# micD21_v51a1.net
KiCad netlist of a schematic drawn in EAGLE
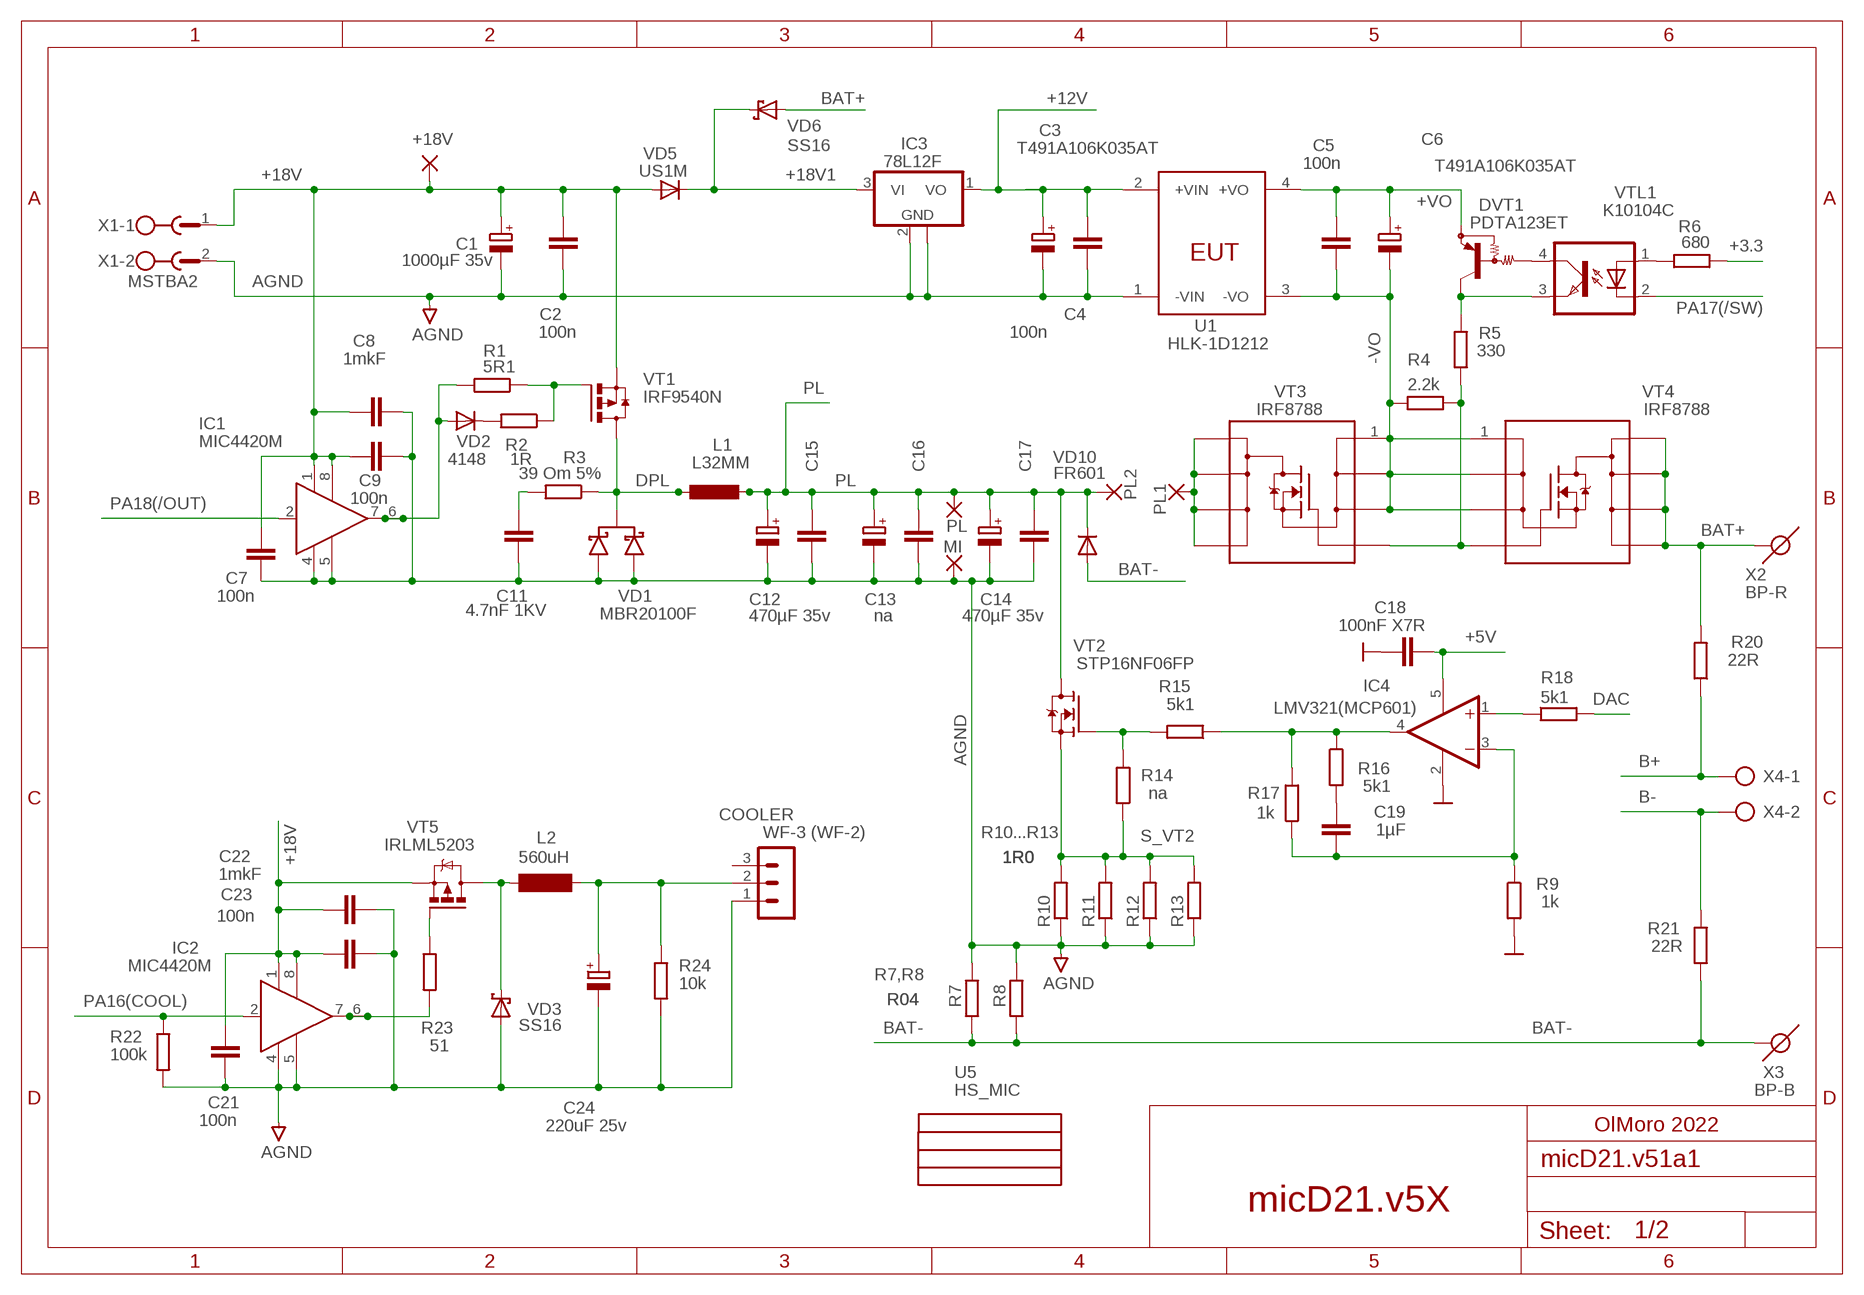
[diagram p0: schematic, sheet 1]
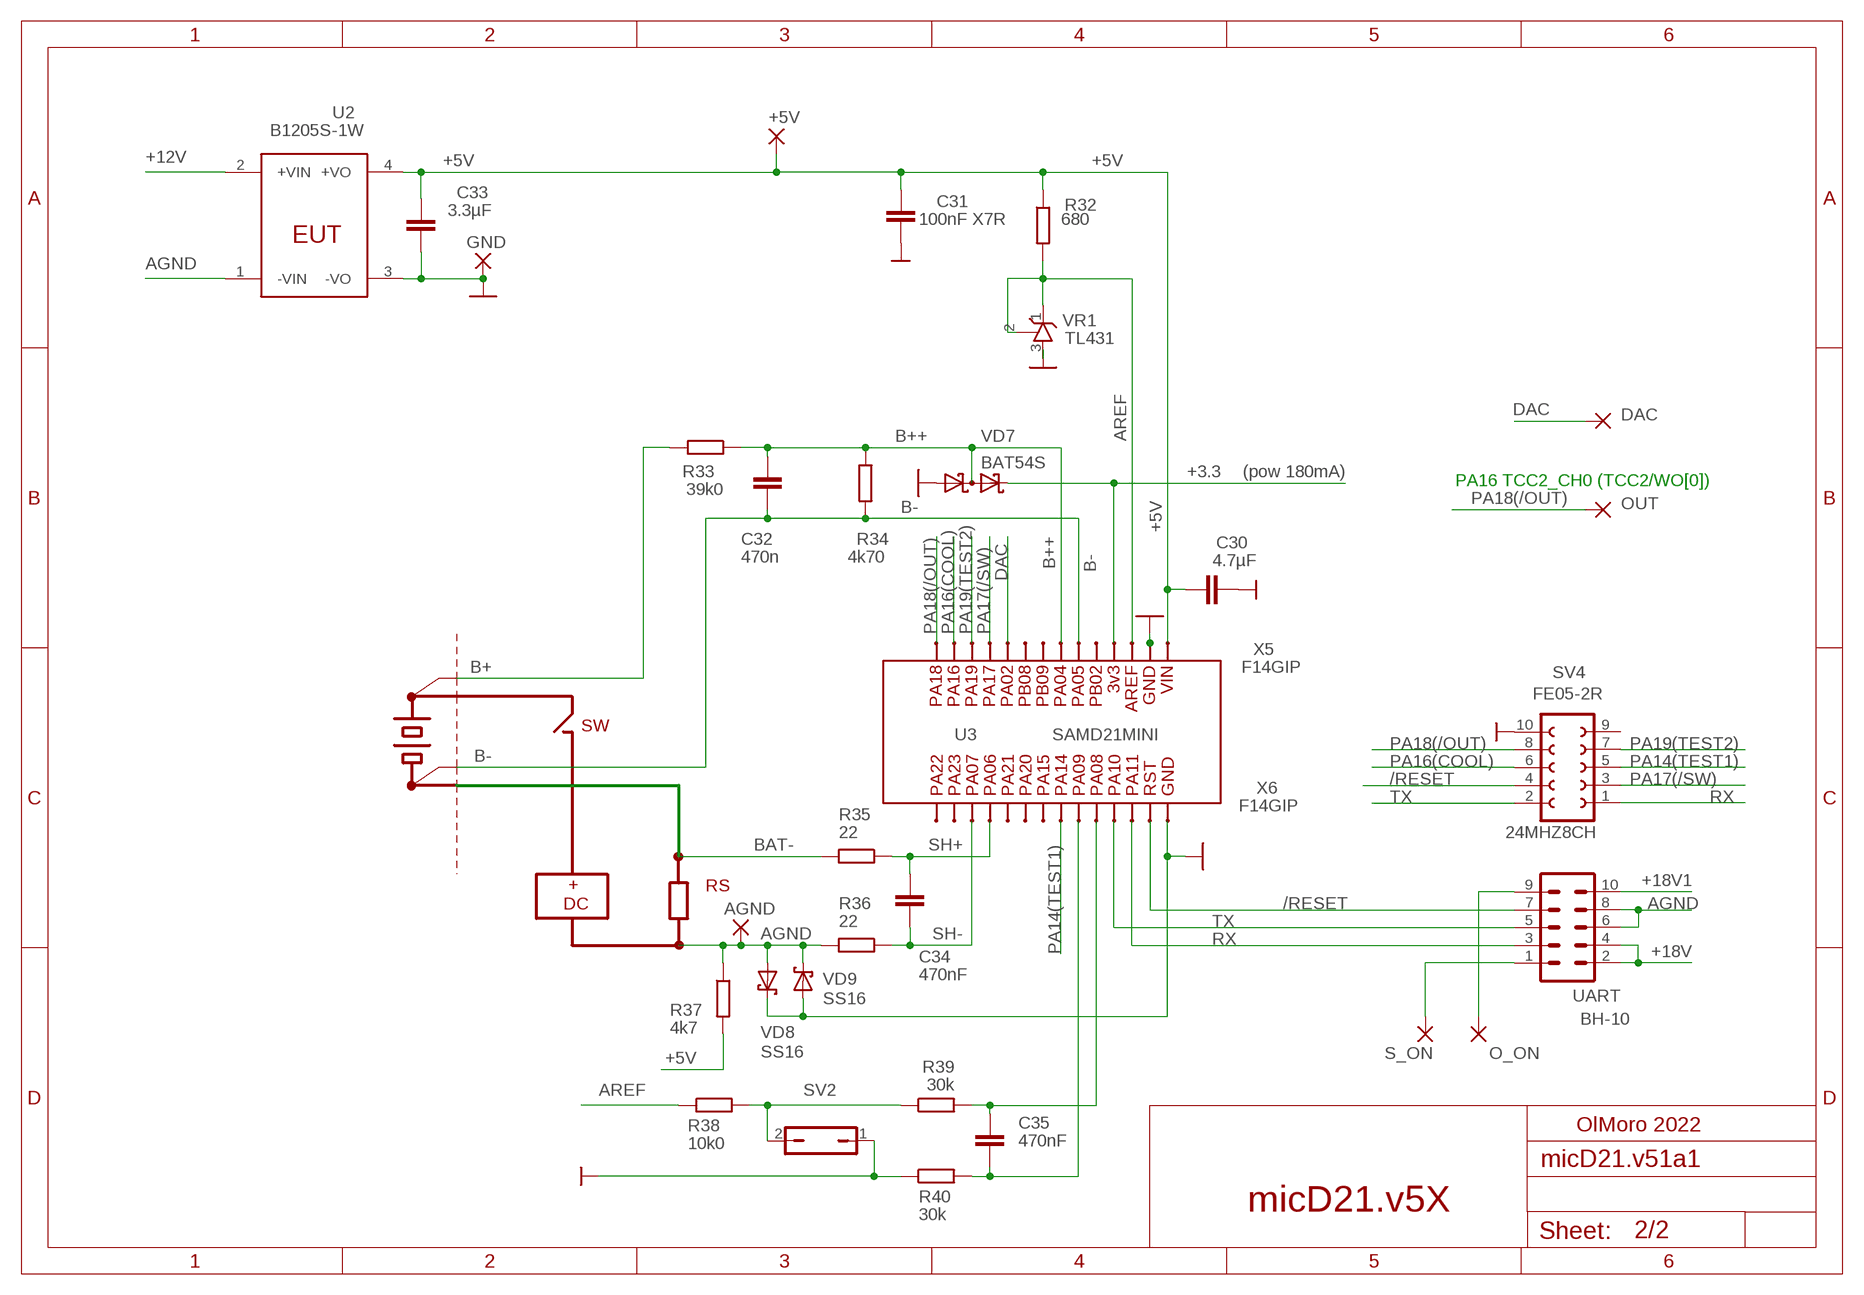
[diagram p1: schematic, sheet 2]

(export (version "E")
  (design (tool "Eeschema 10.0.6"))
  (components
    (comp (ref "+5V")
      (value "WIREPAD1,6/0,8")
      (footprint "eagle-import:1,6_0,8")
      (libsource (lib "eagle-import") (part "WIREPAD1,6/0,8"))
    )
    (comp (ref "24MHZ8CH")
      (value "DIAGNOSTICS")
      (footprint "eagle-import:DIAGNOSTICS")
      (libsource (lib "eagle-import") (part "DIAGNOSTICS"))
    )
    (comp (ref "AGND")
      (value "AGND")
      (footprint "eagle-import:4,16O1,6")
      (libsource (lib "eagle-import") (part "WIREPAD4,16O1,6"))
    )
    (comp (ref "C30")
      (value "4.7µF")
      (footprint "eagle-import:C0805")
      (libsource (lib "eagle-import") (part "C-EUC0805"))
    )
    (comp (ref "C31")
      (value "100nF X7R")
      (footprint "eagle-import:C0603")
      (libsource (lib "eagle-import") (part "C-EUC0603"))
    )
    (comp (ref "C32")
      (value "470n")
      (footprint "eagle-import:C0603")
      (libsource (lib "eagle-import") (part "C-EUC0603"))
    )
    (comp (ref "C33")
      (value "3.3µF")
      (footprint "eagle-import:C0805")
      (libsource (lib "eagle-import") (part "C-EUC0805"))
    )
    (comp (ref "C34")
      (value "470nF")
      (footprint "eagle-import:C0603")
      (libsource (lib "eagle-import") (part "C-EUC0603"))
    )
    (comp (ref "C35")
      (value "470nF")
      (footprint "eagle-import:C0805")
      (libsource (lib "eagle-import") (part "C-EUC0805"))
    )
    (comp (ref "DAC")
      (value "WIREPAD1,6/0,8")
      (footprint "eagle-import:1,6_0,8")
      (libsource (lib "eagle-import") (part "WIREPAD1,6/0,8"))
    )
    (comp (ref "GND")
      (value "GND")
      (footprint "eagle-import:4,16O1,6")
      (libsource (lib "eagle-import") (part "WIREPAD4,16O1,6"))
    )
    (comp (ref "OUT")
      (value "WIREPAD1,6/0,8")
      (footprint "eagle-import:1,6_0,8")
      (libsource (lib "eagle-import") (part "WIREPAD1,6/0,8"))
    )
    (comp (ref "O_ON")
      (value "WIREPAD1,6/0,8")
      (footprint "eagle-import:1,6_0,8")
      (libsource (lib "eagle-import") (part "WIREPAD1,6/0,8"))
    )
    (comp (ref "R32")
      (value "680")
      (footprint "eagle-import:R0603")
      (libsource (lib "eagle-import") (part "R-EU_R0603"))
    )
    (comp (ref "R33")
      (value "39k0")
      (footprint "eagle-import:R0603")
      (libsource (lib "eagle-import") (part "R-EU_R0603"))
    )
    (comp (ref "R34")
      (value "4k70")
      (footprint "eagle-import:R0603")
      (libsource (lib "eagle-import") (part "R-EU_R0603"))
    )
    (comp (ref "R35")
      (value "22")
      (footprint "eagle-import:R0603")
      (libsource (lib "eagle-import") (part "R-EU_R0603"))
    )
    (comp (ref "R36")
      (value "22")
      (footprint "eagle-import:R0603")
      (libsource (lib "eagle-import") (part "R-EU_R0603"))
    )
    (comp (ref "R37")
      (value "4k7")
      (footprint "eagle-import:R0603")
      (libsource (lib "eagle-import") (part "R-EU_R0603"))
    )
    (comp (ref "R38")
      (value "10k0")
      (footprint "eagle-import:R0603")
      (libsource (lib "eagle-import") (part "R-EU_R0603"))
    )
    (comp (ref "R39")
      (value "30k")
      (footprint "eagle-import:R0603")
      (libsource (lib "eagle-import") (part "R-EU_R0603"))
    )
    (comp (ref "R40")
      (value "30k")
      (footprint "eagle-import:R0603")
      (libsource (lib "eagle-import") (part "R-EU_R0603"))
    )
    (comp (ref "SV2")
      (value "JP1Q")
      (footprint "eagle-import:JP1")
      (libsource (lib "eagle-import") (part "JP1Q"))
    )
    (comp (ref "SV4")
      (value "FE05-2R")
      (footprint "eagle-import:FE05-2R")
      (libsource (lib "eagle-import") (part "FE05-2R"))
    )
    (comp (ref "S_ON")
      (value "WIREPAD1,6/0,8")
      (footprint "eagle-import:1,6_0,8")
      (libsource (lib "eagle-import") (part "WIREPAD1,6/0,8"))
    )
    (comp (ref "U2")
      (value "B1205S-1W")
      (footprint "eagle-import:HLK-1D1212")
      (libsource (lib "eagle-import") (part "HLK-1D1212"))
    )
    (comp (ref "U3")
      (value "SAMD21MINI")
      (footprint "eagle-import:SAMD21MINI")
      (libsource (lib "eagle-import") (part "SAMD21MINI"))
    )
    (comp (ref "UART")
      (value "BH-10")
      (footprint "eagle-import:ML10")
      (libsource (lib "eagle-import") (part "ML10"))
    )
    (comp (ref "VD7")
      (value "BAT54S")
      (footprint "eagle-import:SOT23")
      (libsource (lib "eagle-import") (part "BAT54S"))
    )
    (comp (ref "VD8")
      (value "SS16")
      (footprint "eagle-import:DO214AC")
      (libsource (lib "eagle-import") (part "SS16"))
    )
    (comp (ref "VD9")
      (value "SS16")
      (footprint "eagle-import:DO214AC")
      (libsource (lib "eagle-import") (part "SS16"))
    )
    (comp (ref "VR1")
      (value "TL431")
      (footprint "eagle-import:SOT23")
      (libsource (lib "eagle-import") (part "TL431-SOT23-3"))
    )
    (comp (ref "X5")
      (value "F14GIP")
      (footprint "eagle-import:F14GIP")
      (libsource (lib "eagle-import") (part "F14GIP"))
    )
    (comp (ref "X6")
      (value "F14GIP")
      (footprint "eagle-import:F14GIP")
      (libsource (lib "eagle-import") (part "F14GIP"))
    )
    (comp (ref "+18V")
      (value "WIREPAD1,6/0,8")
      (footprint "eagle-import:1,6_0,8")
      (libsource (lib "eagle-import") (part "WIREPAD1,6/0,8"))
    )
    (comp (ref "C1")
      (value "1000µF 35v")
      (footprint "eagle-import:E5-10,5")
      (libsource (lib "eagle-import") (part "CPOL-EUE5-10.5"))
    )
    (comp (ref "C2")
      (value "100n")
      (footprint "eagle-import:C0805")
      (libsource (lib "eagle-import") (part "C-EUC0805"))
    )
    (comp (ref "C3")
      (value "T491A106K035AT")
      (footprint "eagle-import:CT3528")
      (libsource (lib "eagle-import") (part "CPOL-EUCT3528"))
    )
    (comp (ref "C4")
      (value "100n")
      (footprint "eagle-import:C0603")
      (libsource (lib "eagle-import") (part "C-EUC0603"))
    )
    (comp (ref "C5")
      (value "100n")
      (footprint "eagle-import:C0603")
      (libsource (lib "eagle-import") (part "C-EUC0603"))
    )
    (comp (ref "C6")
      (value "T491A106K035AT")
      (footprint "eagle-import:CT3528")
      (libsource (lib "eagle-import") (part "CPOL-EUCT3528"))
    )
    (comp (ref "C7")
      (value "100n")
      (footprint "eagle-import:C0603")
      (libsource (lib "eagle-import") (part "C-EUC0603"))
    )
    (comp (ref "C8")
      (value "1mkF")
      (footprint "eagle-import:C0603")
      (libsource (lib "eagle-import") (part "C-EUC0603"))
    )
    (comp (ref "C9")
      (value "100n")
      (footprint "eagle-import:C0603")
      (libsource (lib "eagle-import") (part "C-EUC0603"))
    )
    (comp (ref "C11")
      (value "4.7nF 1KV")
      (footprint "eagle-import:C102-064X133")
      (libsource (lib "eagle-import") (part "C-EU102-064X133"))
    )
    (comp (ref "C12")
      (value "470µF 35v")
      (footprint "eagle-import:E5-10,5")
      (libsource (lib "eagle-import") (part "CPOL-EUE5-10.5"))
    )
    (comp (ref "C13")
      (value "na")
      (footprint "eagle-import:E5-13")
      (libsource (lib "eagle-import") (part "CPOL-EUE5-13"))
    )
    (comp (ref "C14")
      (value "470µF 35v")
      (footprint "eagle-import:E5-10,5")
      (libsource (lib "eagle-import") (part "CPOL-EUE5-10.5"))
    )
    (comp (ref "C15")
      (value "1mkF")
      (footprint "eagle-import:C0805")
      (libsource (lib "eagle-import") (part "C-EUC0805"))
    )
    (comp (ref "C16")
      (value "1mkF")
      (footprint "eagle-import:C0805")
      (libsource (lib "eagle-import") (part "C-EUC0805"))
    )
    (comp (ref "C17")
      (value "1mkF")
      (footprint "eagle-import:C0805")
      (libsource (lib "eagle-import") (part "C-EUC0805"))
    )
    (comp (ref "C18")
      (value "100nF X7R")
      (footprint "eagle-import:C0603")
      (libsource (lib "eagle-import") (part "C-EUC0603"))
    )
    (comp (ref "C19")
      (value "1µF")
      (footprint "eagle-import:C0603")
      (libsource (lib "eagle-import") (part "C-EUC0603"))
    )
    (comp (ref "C21")
      (value "100n")
      (footprint "eagle-import:C0603")
      (libsource (lib "eagle-import") (part "C-EUC0603"))
    )
    (comp (ref "C22")
      (value "1mkF")
      (footprint "eagle-import:C0603")
      (libsource (lib "eagle-import") (part "C-EUC0603"))
    )
    (comp (ref "C23")
      (value "100n")
      (footprint "eagle-import:C0603")
      (libsource (lib "eagle-import") (part "C-EUC0603"))
    )
    (comp (ref "C24")
      (value "220uF 25v")
      (footprint "eagle-import:E5-8,5")
      (libsource (lib "eagle-import") (part "CPOL-EUE5-8.5"))
    )
    (comp (ref "COOLER")
      (value "WF-3 (WF-2)")
      (footprint "eagle-import:WF-3")
      (libsource (lib "eagle-import") (part "WF-3"))
    )
    (comp (ref "DVT1")
      (value "PDTA123ET")
      (footprint "eagle-import:SC59-BEC")
      (libsource (lib "eagle-import") (part "MUN2113T1"))
    )
    (comp (ref "IC1")
      (value "MIC4420M")
      (footprint "eagle-import:SO-08")
      (libsource (lib "eagle-import") (part "MIC4420M"))
    )
    (comp (ref "IC2")
      (value "MIC4420M")
      (footprint "eagle-import:SO-08")
      (libsource (lib "eagle-import") (part "MIC4420M"))
    )
    (comp (ref "IC3")
      (value "78L12F")
      (footprint "eagle-import:SOT89")
      (libsource (lib "eagle-import") (part "78LF12"))
    )
    (comp (ref "IC4")
      (value "LMV321(MCP601)")
      (footprint "eagle-import:SOT23-5")
      (libsource (lib "eagle-import") (part "LM321?MF"))
    )
    (comp (ref "L1")
      (value "L32MM")
      (footprint "eagle-import:L22MM")
      (libsource (lib "eagle-import") (part "L32MM"))
    )
    (comp (ref "L2")
      (value "560uH")
      (footprint "eagle-import:BS11")
      (libsource (lib "eagle-import") (part "BS11"))
    )
    (comp (ref "MI")
      (value "WIREPAD4,16O1,6")
      (footprint "eagle-import:4,16O1,6")
      (libsource (lib "eagle-import") (part "WIREPAD4,16O1,6"))
    )
    (comp (ref "PL")
      (value "WIREPAD4,16O1,6")
      (footprint "eagle-import:4,16O1,6")
      (libsource (lib "eagle-import") (part "WIREPAD4,16O1,6"))
    )
    (comp (ref "PL1")
      (value "WIREPAD2,54/0,8")
      (footprint "eagle-import:2,54_0,8")
      (libsource (lib "eagle-import") (part "WIREPAD2,54/0,8"))
    )
    (comp (ref "PL2")
      (value "WIREPAD2,54/0,8")
      (footprint "eagle-import:2,54_0,8")
      (libsource (lib "eagle-import") (part "WIREPAD2,54/0,8"))
    )
    (comp (ref "R1")
      (value "5R1")
      (footprint "eagle-import:R0805")
      (libsource (lib "eagle-import") (part "R-EU_R0805"))
    )
    (comp (ref "R2")
      (value "1R")
      (footprint "eagle-import:R0805")
      (libsource (lib "eagle-import") (part "R-EU_R0805"))
    )
    (comp (ref "R3")
      (value "39 Om 5%")
      (footprint "eagle-import:0515_20")
      (libsource (lib "eagle-import") (part "R-0515/20"))
    )
    (comp (ref "R4")
      (value "2.2k")
      (footprint "eagle-import:R0603")
      (libsource (lib "eagle-import") (part "R-EU_R0603"))
    )
    (comp (ref "R5")
      (value "330")
      (footprint "eagle-import:R0603")
      (libsource (lib "eagle-import") (part "R-EU_R0603"))
    )
    (comp (ref "R6")
      (value "680")
      (footprint "eagle-import:R0603")
      (libsource (lib "eagle-import") (part "R-EU_R0603"))
    )
    (comp (ref "R7")
      (value "R04")
      (footprint "eagle-import:R2512")
      (libsource (lib "eagle-import") (part "R-EU_R2512"))
    )
    (comp (ref "R8")
      (value "R04")
      (footprint "eagle-import:R2512")
      (libsource (lib "eagle-import") (part "R-EU_R2512"))
    )
    (comp (ref "R9")
      (value "1k")
      (footprint "eagle-import:R0603")
      (libsource (lib "eagle-import") (part "R-EU_R0603"))
    )
    (comp (ref "R10")
      (value "1R0")
      (footprint "eagle-import:R2512")
      (libsource (lib "eagle-import") (part "R-EU_R2512"))
    )
    (comp (ref "R11")
      (value "1R0")
      (footprint "eagle-import:R2512")
      (libsource (lib "eagle-import") (part "R-EU_R2512"))
    )
    (comp (ref "R12")
      (value "1R0")
      (footprint "eagle-import:R2512")
      (libsource (lib "eagle-import") (part "R-EU_R2512"))
    )
    (comp (ref "R13")
      (value "1R0")
      (footprint "eagle-import:R2512")
      (libsource (lib "eagle-import") (part "R-EU_R2512"))
    )
    (comp (ref "R14")
      (value "na")
      (footprint "eagle-import:R0603")
      (libsource (lib "eagle-import") (part "R-EU_R0603"))
    )
    (comp (ref "R15")
      (value "5k1")
      (footprint "eagle-import:R0603")
      (libsource (lib "eagle-import") (part "R-EU_R0603"))
    )
    (comp (ref "R16")
      (value "5k1")
      (footprint "eagle-import:R0603")
      (libsource (lib "eagle-import") (part "R-EU_R0603"))
    )
    (comp (ref "R17")
      (value "1k")
      (footprint "eagle-import:R0603")
      (libsource (lib "eagle-import") (part "R-EU_R0603"))
    )
    (comp (ref "R18")
      (value "5k1")
      (footprint "eagle-import:R0603")
      (libsource (lib "eagle-import") (part "R-EU_R0603"))
    )
    (comp (ref "R20")
      (value "22R")
      (footprint "eagle-import:R0603")
      (libsource (lib "eagle-import") (part "R-EU_R0603"))
    )
    (comp (ref "R21")
      (value "22R")
      (footprint "eagle-import:R0603")
      (libsource (lib "eagle-import") (part "R-EU_R0603"))
    )
    (comp (ref "R22")
      (value "100k")
      (footprint "eagle-import:R0603")
      (libsource (lib "eagle-import") (part "R-EU_R0603"))
    )
    (comp (ref "R23")
      (value "51")
      (footprint "eagle-import:R0603")
      (libsource (lib "eagle-import") (part "R-EU_R0603"))
    )
    (comp (ref "R24")
      (value "10k")
      (footprint "eagle-import:R0603")
      (libsource (lib "eagle-import") (part "R-EU_R0603"))
    )
    (comp (ref "U1")
      (value "HLK-1D1212")
      (footprint "eagle-import:HLK-1D1212")
      (libsource (lib "eagle-import") (part "HLK-1D1212"))
    )
    (comp (ref "U5")
      (value "HS_MIC")
      (footprint "eagle-import:HS-MIC")
      (libsource (lib "eagle-import") (part "HS_MIC"))
    )
    (comp (ref "VD1")
      (value "MBR20100F")
      (footprint "eagle-import:ITO220J")
      (libsource (lib "eagle-import") (part "MBR20100F"))
    )
    (comp (ref "VD2")
      (value "4148")
      (footprint "eagle-import:SMADIODE")
      (libsource (lib "eagle-import") (part "DIODESMA"))
    )
    (comp (ref "VD3")
      (value "SS16")
      (footprint "eagle-import:DO214AC")
      (libsource (lib "eagle-import") (part "SS16"))
    )
    (comp (ref "VD5")
      (value "US1M")
      (footprint "eagle-import:DO214AC")
      (libsource (lib "eagle-import") (part "US1M"))
    )
    (comp (ref "VD6")
      (value "SS16")
      (footprint "eagle-import:DO214AC")
      (libsource (lib "eagle-import") (part "SS16"))
    )
    (comp (ref "VD10")
      (value "FR601")
      (footprint "eagle-import:DIODE-1_P6-15")
      (libsource (lib "eagle-import") (part "DIODE-1_DIODE-P6-15"))
    )
    (comp (ref "VT1")
      (value "IRF9540N")
      (footprint "eagle-import:TO-220FP")
      (libsource (lib "eagle-import") (part "IRF9540N"))
    )
    (comp (ref "VT2")
      (value "STP16NF06FP")
      (footprint "eagle-import:TO-220FP")
      (libsource (lib "eagle-import") (part "STP16NF06FP"))
    )
    (comp (ref "VT3")
      (value "IRF8788")
      (footprint "eagle-import:SO-8")
      (libsource (lib "eagle-import") (part "IRF8788"))
    )
    (comp (ref "VT4")
      (value "IRF8788")
      (footprint "eagle-import:SO-8")
      (libsource (lib "eagle-import") (part "IRF8788"))
    )
    (comp (ref "VT5")
      (value "IRLML5203")
      (footprint "eagle-import:MICRO3")
      (libsource (lib "eagle-import") (part "IRLML5203"))
    )
    (comp (ref "VTL1")
      (value "K10104C")
      (footprint "eagle-import:SMD4-7")
      (libsource (lib "eagle-import") (part "SFH618?A-3X007"))
    )
    (comp (ref "X1")
      (value "MSTBA2")
      (footprint "eagle-import:MSTBA2")
      (fields (field (name "MF") "FARNELL") (field (name "MPN") "1757242"))
      (libsource (lib "eagle-import") (part "MSTBA2"))
    )
    (comp (ref "X2")
      (value "BP-R")
      (footprint "eagle-import:BP-R")
      (libsource (lib "eagle-import") (part "BP-R"))
    )
    (comp (ref "X3")
      (value "BP-B")
      (footprint "eagle-import:BP-B")
      (libsource (lib "eagle-import") (part "BP-B"))
    )
    (comp (ref "X4")
      (value "AK500/2-H")
      (footprint "eagle-import:AK500_2-H")
      (libsource (lib "eagle-import") (part "AK500/2-H"))
    )
  )
  (nets
    (net (code "1") (name "+3.3") (class "Default")
      (node (ref "R6") (pin "1") (pinfunction "1_1") (pintype "passive"))
      (node (ref "VD7") (pin "2") (pinfunction "C2_2") (pintype "passive"))
      (node (ref "X5") (pin "4") (pinfunction "4_4") (pintype "passive"))
    )
    (net (code "2") (name "+5V") (class "Default")
      (node (ref "+5V") (pin "1") (pinfunction "P_1") (pintype "passive"))
      (node (ref "C18") (pin "2") (pinfunction "2_2") (pintype "passive"))
      (node (ref "C30") (pin "1") (pinfunction "1_1") (pintype "passive"))
      (node (ref "C31") (pin "1") (pinfunction "1_1") (pintype "passive"))
      (node (ref "C33") (pin "1") (pinfunction "1_1") (pintype "passive"))
      (node (ref "IC4") (pin "5") (pinfunction "V+_5") (pintype "power_in"))
      (node (ref "R32") (pin "1") (pinfunction "1_1") (pintype "passive"))
      (node (ref "R37") (pin "2") (pinfunction "2_2") (pintype "passive"))
      (node (ref "U2") (pin "4") (pinfunction "+VO_4") (pintype "power_in"))
      (node (ref "X5") (pin "1") (pinfunction "1_1") (pintype "passive"))
    )
    (net (code "3") (name "+12V") (class "Default")
      (node (ref "C3") (pin "+") (pinfunction "+_+") (pintype "passive"))
      (node (ref "C4") (pin "2") (pinfunction "2_2") (pintype "passive"))
      (node (ref "IC3") (pin "1") (pinfunction "VO_1") (pintype "passive"))
      (node (ref "U1") (pin "2") (pinfunction "+VIN_2") (pintype "power_in"))
      (node (ref "U2") (pin "2") (pinfunction "+VIN_2") (pintype "power_in"))
    )
    (net (code "4") (name "+18V") (class "Default")
      (node (ref "+18V") (pin "1") (pinfunction "P_1") (pintype "passive"))
      (node (ref "C1") (pin "+") (pinfunction "+_+") (pintype "passive"))
      (node (ref "C2") (pin "2") (pinfunction "2_2") (pintype "passive"))
      (node (ref "C21") (pin "2") (pinfunction "2_2") (pintype "passive"))
      (node (ref "C22") (pin "2") (pinfunction "2_2") (pintype "passive"))
      (node (ref "C23") (pin "2") (pinfunction "2_2") (pintype "passive"))
      (node (ref "C7") (pin "2") (pinfunction "2_2") (pintype "passive"))
      (node (ref "C8") (pin "2") (pinfunction "2_2") (pintype "passive"))
      (node (ref "C9") (pin "2") (pinfunction "2_2") (pintype "passive"))
      (node (ref "IC1") (pin "1") (pinfunction "VS_1") (pintype "power_in"))
      (node (ref "IC1") (pin "8") (pinfunction "VS1_8") (pintype "power_in"))
      (node (ref "IC2") (pin "1") (pinfunction "VS_1") (pintype "power_in"))
      (node (ref "IC2") (pin "8") (pinfunction "VS1_8") (pintype "power_in"))
      (node (ref "UART") (pin "2") (pinfunction "2_2") (pintype "passive"))
      (node (ref "UART") (pin "4") (pinfunction "4_4") (pintype "passive"))
      (node (ref "VD5") (pin "A") (pinfunction "A_A") (pintype "passive"))
      (node (ref "VT1") (pin "3") (pinfunction "S_3") (pintype "passive"))
      (node (ref "VT5") (pin "2") (pinfunction "S_2") (pintype "passive"))
      (node (ref "X1") (pin "1") (pinfunction "1_1") (pintype "passive"))
    )
    (net (code "5") (name "+18V1") (class "Default")
      (node (ref "IC3") (pin "3") (pinfunction "VI_3") (pintype "input"))
      (node (ref "UART") (pin "10") (pinfunction "10_10") (pintype "passive"))
      (node (ref "VD5") (pin "C") (pinfunction "C_C") (pintype "passive"))
      (node (ref "VD6") (pin "C") (pinfunction "C_C") (pintype "passive"))
    )
    (net (code "6") (name "+VO") (class "Default")
      (node (ref "C5") (pin "2") (pinfunction "2_2") (pintype "passive"))
      (node (ref "C6") (pin "+") (pinfunction "+_+") (pintype "passive"))
      (node (ref "DVT1") (pin "E") (pinfunction "E_E") (pintype "passive"))
      (node (ref "U1") (pin "4") (pinfunction "+VO_4") (pintype "power_in"))
    )
    (net (code "7") (name "-VO") (class "Default")
      (node (ref "C5") (pin "1") (pinfunction "1_1") (pintype "passive"))
      (node (ref "C6") (pin "-") (pinfunction "-_-") (pintype "passive"))
      (node (ref "R4") (pin "2") (pinfunction "2_2") (pintype "passive"))
      (node (ref "U1") (pin "3") (pinfunction "-VO_3") (pintype "power_in"))
      (node (ref "VT3") (pin "1") (pinfunction "S_1") (pintype "passive"))
      (node (ref "VT3") (pin "2") (pinfunction "S_2") (pintype "passive"))
      (node (ref "VT3") (pin "3") (pinfunction "S_3") (pintype "passive"))
      (node (ref "VT4") (pin "1") (pinfunction "S_1") (pintype "passive"))
      (node (ref "VT4") (pin "2") (pinfunction "S_2") (pintype "passive"))
      (node (ref "VT4") (pin "3") (pinfunction "S_3") (pintype "passive"))
    )
    (net (code "8") (name "AGND") (class "Default")
      (node (ref "AGND") (pin "1") (pinfunction "P_1") (pintype "passive"))
      (node (ref "C1") (pin "-") (pinfunction "-_-") (pintype "passive"))
      (node (ref "C11") (pin "2") (pinfunction "2_2") (pintype "passive"))
      (node (ref "C12") (pin "-") (pinfunction "-_-") (pintype "passive"))
      (node (ref "C13") (pin "-") (pinfunction "-_-") (pintype "passive"))
      (node (ref "C14") (pin "-") (pinfunction "-_-") (pintype "passive"))
      (node (ref "C15") (pin "2") (pinfunction "2_2") (pintype "passive"))
      (node (ref "C16") (pin "2") (pinfunction "2_2") (pintype "passive"))
      (node (ref "C17") (pin "2") (pinfunction "2_2") (pintype "passive"))
      (node (ref "C2") (pin "1") (pinfunction "1_1") (pintype "passive"))
      (node (ref "C21") (pin "1") (pinfunction "1_1") (pintype "passive"))
      (node (ref "C22") (pin "1") (pinfunction "1_1") (pintype "passive"))
      (node (ref "C23") (pin "1") (pinfunction "1_1") (pintype "passive"))
      (node (ref "C24") (pin "-") (pinfunction "-_-") (pintype "passive"))
      (node (ref "C3") (pin "-") (pinfunction "-_-") (pintype "passive"))
      (node (ref "C4") (pin "1") (pinfunction "1_1") (pintype "passive"))
      (node (ref "C7") (pin "1") (pinfunction "1_1") (pintype "passive"))
      (node (ref "C8") (pin "1") (pinfunction "1_1") (pintype "passive"))
      (node (ref "C9") (pin "1") (pinfunction "1_1") (pintype "passive"))
      (node (ref "COOLER") (pin "1") (pinfunction "1_1") (pintype "passive"))
      (node (ref "IC1") (pin "4") (pinfunction "GND_4") (pintype "power_in"))
      (node (ref "IC1") (pin "5") (pinfunction "GND1_5") (pintype "power_in"))
      (node (ref "IC2") (pin "4") (pinfunction "GND_4") (pintype "power_in"))
      (node (ref "IC2") (pin "5") (pinfunction "GND1_5") (pintype "power_in"))
      (node (ref "IC3") (pin "2") (pinfunction "GND_2") (pintype "passive"))
      (node (ref "IC3") (pin "2@1") (pinfunction "GND_2@1") (pintype "passive"))
      (node (ref "MI") (pin "1") (pinfunction "P_1") (pintype "passive"))
      (node (ref "R10") (pin "1") (pinfunction "1_1") (pintype "passive"))
      (node (ref "R11") (pin "1") (pinfunction "1_1") (pintype "passive"))
      (node (ref "R12") (pin "1") (pinfunction "1_1") (pintype "passive"))
      (node (ref "R13") (pin "1") (pinfunction "1_1") (pintype "passive"))
      (node (ref "R22") (pin "2") (pinfunction "2_2") (pintype "passive"))
      (node (ref "R24") (pin "2") (pinfunction "2_2") (pintype "passive"))
      (node (ref "R36") (pin "2") (pinfunction "2_2") (pintype "passive"))
      (node (ref "R37") (pin "1") (pinfunction "1_1") (pintype "passive"))
      (node (ref "R7") (pin "2") (pinfunction "2_2") (pintype "passive"))
      (node (ref "R8") (pin "2") (pinfunction "2_2") (pintype "passive"))
      (node (ref "U1") (pin "1") (pinfunction "-VIN_1") (pintype "power_in"))
      (node (ref "U2") (pin "1") (pinfunction "-VIN_1") (pintype "power_in"))
      (node (ref "UART") (pin "6") (pinfunction "6_6") (pintype "passive"))
      (node (ref "UART") (pin "8") (pinfunction "8_8") (pintype "passive"))
      (node (ref "VD1") (pin "1") (pinfunction "A1_1") (pintype "passive"))
      (node (ref "VD1") (pin "3") (pinfunction "A2_3") (pintype "passive"))
      (node (ref "VD3") (pin "A") (pinfunction "A_A") (pintype "passive"))
      (node (ref "VD8") (pin "A") (pinfunction "A_A") (pintype "passive"))
      (node (ref "VD9") (pin "C") (pinfunction "C_C") (pintype "passive"))
      (node (ref "X1") (pin "2") (pinfunction "1_2") (pintype "passive"))
    )
    (net (code "9") (name "AREF") (class "Default")
      (node (ref "R32") (pin "2") (pinfunction "2_2") (pintype "passive"))
      (node (ref "R38") (pin "1") (pinfunction "1_1") (pintype "passive"))
      (node (ref "VR1") (pin "1") (pinfunction "C_1") (pintype "passive"))
      (node (ref "VR1") (pin "2") (pinfunction "R_2") (pintype "passive"))
      (node (ref "X5") (pin "3") (pinfunction "3_3") (pintype "passive"))
    )
    (net (code "10") (name "B+") (class "Default")
      (node (ref "R20") (pin "1") (pinfunction "1_1") (pintype "passive"))
      (node (ref "R33") (pin "2") (pinfunction "2_2") (pintype "passive"))
      (node (ref "X4") (pin "1") (pinfunction "KL_1") (pintype "passive"))
    )
    (net (code "11") (name "B++") (class "Default")
      (node (ref "C32") (pin "1") (pinfunction "1_1") (pintype "passive"))
      (node (ref "R33") (pin "1") (pinfunction "1_1") (pintype "passive"))
      (node (ref "R34") (pin "1") (pinfunction "1_1") (pintype "passive"))
      (node (ref "VD7") (pin "3") (pinfunction "C1A2_3") (pintype "passive"))
      (node (ref "X5") (pin "7") (pinfunction "7_7") (pintype "passive"))
    )
    (net (code "12") (name "B-") (class "Default")
      (node (ref "C32") (pin "2") (pinfunction "2_2") (pintype "passive"))
      (node (ref "R21") (pin "1") (pinfunction "1_1") (pintype "passive"))
      (node (ref "R34") (pin "2") (pinfunction "2_2") (pintype "passive"))
      (node (ref "X4") (pin "2") (pinfunction "KL_2") (pintype "passive"))
      (node (ref "X5") (pin "6") (pinfunction "6_6") (pintype "passive"))
    )
    (net (code "13") (name "BAT+") (class "Default")
      (node (ref "R20") (pin "2") (pinfunction "2_2") (pintype "passive"))
      (node (ref "VD6") (pin "A") (pinfunction "A_A") (pintype "passive"))
      (node (ref "VT4") (pin "5") (pinfunction "D_5") (pintype "passive"))
      (node (ref "VT4") (pin "6") (pinfunction "D_6") (pintype "passive"))
      (node (ref "VT4") (pin "7") (pinfunction "D_7") (pintype "passive"))
      (node (ref "VT4") (pin "8") (pinfunction "D_8") (pintype "passive"))
      (node (ref "X2") (pin "1") (pinfunction "P$1_1") (pintype "passive"))
    )
    (net (code "14") (name "BAT-") (class "Default")
      (node (ref "R21") (pin "2") (pinfunction "2_2") (pintype "passive"))
      (node (ref "R35") (pin "2") (pinfunction "2_2") (pintype "passive"))
      (node (ref "R7") (pin "1") (pinfunction "1_1") (pintype "passive"))
      (node (ref "R8") (pin "1") (pinfunction "1_1") (pintype "passive"))
      (node (ref "VD10") (pin "A") (pinfunction "A_A") (pintype "passive"))
      (node (ref "X3") (pin "1") (pinfunction "P$1_1") (pintype "passive"))
    )
    (net (code "15") (name "DAC") (class "Default")
      (node (ref "DAC") (pin "1") (pinfunction "P_1") (pintype "passive"))
      (node (ref "R18") (pin "2") (pinfunction "2_2") (pintype "passive"))
      (node (ref "X5") (pin "10") (pinfunction "10_10") (pintype "passive"))
    )
    (net (code "16") (name "DPL") (class "Default")
      (node (ref "L1") (pin "2@7") (pinfunction "2_2@7") (pintype "passive"))
      (node (ref "L1") (pin "2@8") (pinfunction "2_2@8") (pintype "passive"))
      (node (ref "R3") (pin "1") (pinfunction "1_1") (pintype "passive"))
      (node (ref "VD1") (pin "2") (pinfunction "C_2") (pintype "passive"))
      (node (ref "VT1") (pin "2") (pinfunction "D_2") (pintype "passive"))
    )
    (net (code "17") (name "GND") (class "Default")
      (node (ref "C18") (pin "1") (pinfunction "1_1") (pintype "passive"))
      (node (ref "C30") (pin "2") (pinfunction "2_2") (pintype "passive"))
      (node (ref "C31") (pin "2") (pinfunction "2_2") (pintype "passive"))
      (node (ref "C33") (pin "2") (pinfunction "2_2") (pintype "passive"))
      (node (ref "GND") (pin "1") (pinfunction "P_1") (pintype "passive"))
      (node (ref "IC4") (pin "2") (pinfunction "V-_2") (pintype "power_in"))
      (node (ref "R40") (pin "1") (pinfunction "1_1") (pintype "passive"))
      (node (ref "R9") (pin "2") (pinfunction "2_2") (pintype "passive"))
      (node (ref "SV2") (pin "1") (pinfunction "1_1") (pintype "passive"))
      (node (ref "SV4") (pin "10") (pinfunction "10_10") (pintype "passive"))
      (node (ref "U2") (pin "3") (pinfunction "-VO_3") (pintype "power_in"))
      (node (ref "VD7") (pin "1") (pinfunction "A1_1") (pintype "passive"))
      (node (ref "VD8") (pin "C") (pinfunction "C_C") (pintype "passive"))
      (node (ref "VD9") (pin "A") (pinfunction "A_A") (pintype "passive"))
      (node (ref "VR1") (pin "3") (pinfunction "A_3") (pintype "passive"))
      (node (ref "X5") (pin "2") (pinfunction "2_2") (pintype "passive"))
      (node (ref "X6") (pin "14") (pinfunction "14_14") (pintype "passive"))
    )
    (net (code "18") (name "Net-(C11-Pad1)") (class "Default")
      (node (ref "C11") (pin "1") (pinfunction "1_1") (pintype "passive"))
      (node (ref "R3") (pin "2") (pinfunction "2_2") (pintype "passive"))
    )
    (net (code "19") (name "Net-(C19-Pad1)") (class "Default")
      (node (ref "C19") (pin "1") (pinfunction "1_1") (pintype "passive"))
      (node (ref "R16") (pin "2") (pinfunction "2_2") (pintype "passive"))
    )
    (net (code "20") (name "Net-(C24-Pad+)") (class "Default")
      (node (ref "C24") (pin "+") (pinfunction "+_+") (pintype "passive"))
      (node (ref "COOLER") (pin "2") (pinfunction "2_2") (pintype "passive"))
      (node (ref "L2") (pin "2") (pinfunction "2_2") (pintype "passive"))
      (node (ref "R24") (pin "1") (pinfunction "1_1") (pintype "passive"))
    )
    (net (code "21") (name "Net-(C35-Pad1)") (class "Default")
      (node (ref "C35") (pin "1") (pinfunction "1_1") (pintype "passive"))
      (node (ref "R39") (pin "2") (pinfunction "2_2") (pintype "passive"))
      (node (ref "X6") (pin "10") (pinfunction "10_10") (pintype "passive"))
    )
    (net (code "22") (name "Net-(C35-Pad2)") (class "Default")
      (node (ref "C35") (pin "2") (pinfunction "2_2") (pintype "passive"))
      (node (ref "R40") (pin "2") (pinfunction "2_2") (pintype "passive"))
      (node (ref "X6") (pin "9") (pinfunction "9_9") (pintype "passive"))
    )
    (net (code "23") (name "Net-(IC1-OUT-Pad6)") (class "Default")
      (node (ref "IC1") (pin "6") (pinfunction "OUT_6") (pintype "passive"))
      (node (ref "IC1") (pin "7") (pinfunction "OUT_7") (pintype "passive"))
      (node (ref "R1") (pin "2") (pinfunction "2_2") (pintype "passive"))
      (node (ref "VD2") (pin "A") (pinfunction "A_A") (pintype "passive"))
    )
    (net (code "24") (name "Net-(IC2-OUT-Pad6)") (class "Default")
      (node (ref "IC2") (pin "6") (pinfunction "OUT_6") (pintype "passive"))
      (node (ref "IC2") (pin "7") (pinfunction "OUT_7") (pintype "passive"))
      (node (ref "R23") (pin "2") (pinfunction "2_2") (pintype "passive"))
    )
    (net (code "25") (name "Net-(IC4-+IN)") (class "Default")
      (node (ref "IC4") (pin "1") (pinfunction "+IN_1") (pintype "input"))
      (node (ref "R18") (pin "1") (pinfunction "1_1") (pintype "passive"))
    )
    (net (code "26") (name "Net-(IC4--IN)") (class "Default")
      (node (ref "C19") (pin "2") (pinfunction "2_2") (pintype "passive"))
      (node (ref "IC4") (pin "3") (pinfunction "-IN_3") (pintype "input"))
      (node (ref "R17") (pin "1") (pinfunction "1_1") (pintype "passive"))
      (node (ref "R9") (pin "1") (pinfunction "1_1") (pintype "passive"))
    )
    (net (code "27") (name "Net-(IC4-OUT)") (class "Default")
      (node (ref "IC4") (pin "4") (pinfunction "OUT_4") (pintype "output"))
      (node (ref "R15") (pin "1") (pinfunction "1_1") (pintype "passive"))
      (node (ref "R16") (pin "1") (pinfunction "1_1") (pintype "passive"))
      (node (ref "R17") (pin "2") (pinfunction "2_2") (pintype "passive"))
    )
    (net (code "28") (name "Net-(O_ON-P)") (class "Default")
      (node (ref "O_ON") (pin "1") (pinfunction "P_1") (pintype "passive"))
      (node (ref "UART") (pin "9") (pinfunction "9_9") (pintype "passive"))
    )
    (net (code "29") (name "Net-(PL1-P)") (class "Default")
      (node (ref "PL1") (pin "1") (pinfunction "P_1") (pintype "passive"))
      (node (ref "VT3") (pin "5") (pinfunction "D_5") (pintype "passive"))
      (node (ref "VT3") (pin "6") (pinfunction "D_6") (pintype "passive"))
      (node (ref "VT3") (pin "7") (pinfunction "D_7") (pintype "passive"))
      (node (ref "VT3") (pin "8") (pinfunction "D_8") (pintype "passive"))
    )
    (net (code "30") (name "Net-(R2-Pad2)") (class "Default")
      (node (ref "R2") (pin "2") (pinfunction "2_2") (pintype "passive"))
      (node (ref "VD2") (pin "C") (pinfunction "C_C") (pintype "passive"))
    )
    (net (code "31") (name "Net-(R38-Pad2)") (class "Default")
      (node (ref "R38") (pin "2") (pinfunction "2_2") (pintype "passive"))
      (node (ref "R39") (pin "1") (pinfunction "1_1") (pintype "passive"))
      (node (ref "SV2") (pin "2") (pinfunction "2_2") (pintype "passive"))
    )
    (net (code "32") (name "Net-(S_ON-P)") (class "Default")
      (node (ref "S_ON") (pin "1") (pinfunction "P_1") (pintype "passive"))
      (node (ref "UART") (pin "1") (pinfunction "1_1") (pintype "passive"))
    )
    (net (code "33") (name "Net-(VT1-G)") (class "Default")
      (node (ref "R1") (pin "1") (pinfunction "1_1") (pintype "passive"))
      (node (ref "R2") (pin "1") (pinfunction "1_1") (pintype "passive"))
      (node (ref "VT1") (pin "1") (pinfunction "G_1") (pintype "passive"))
    )
    (net (code "34") (name "Net-(VT2-G)") (class "Default")
      (node (ref "R14") (pin "2") (pinfunction "2_2") (pintype "passive"))
      (node (ref "R15") (pin "2") (pinfunction "2_2") (pintype "passive"))
      (node (ref "VT2") (pin "1") (pinfunction "G_1") (pintype "passive"))
    )
    (net (code "35") (name "Net-(VT3-G)") (class "Default")
      (node (ref "R4") (pin "1") (pinfunction "1_1") (pintype "passive"))
      (node (ref "R5") (pin "1") (pinfunction "1_1") (pintype "passive"))
      (node (ref "VT3") (pin "4") (pinfunction "G_4") (pintype "passive"))
      (node (ref "VT4") (pin "4") (pinfunction "G_4") (pintype "passive"))
    )
    (net (code "36") (name "Net-(VT5-D)") (class "Default")
      (node (ref "L2") (pin "1") (pinfunction "1_1") (pintype "passive"))
      (node (ref "VD3") (pin "C") (pinfunction "C_C") (pintype "passive"))
      (node (ref "VT5") (pin "3") (pinfunction "D_3") (pintype "passive"))
    )
    (net (code "37") (name "Net-(VT5-G)") (class "Default")
      (node (ref "R23") (pin "1") (pinfunction "1_1") (pintype "passive"))
      (node (ref "VT5") (pin "1") (pinfunction "G_1") (pintype "passive"))
    )
    (net (code "38") (name "Net-(VTL1-A)") (class "Default")
      (node (ref "R6") (pin "2") (pinfunction "2_2") (pintype "passive"))
      (node (ref "VTL1") (pin "1") (pinfunction "A_1") (pintype "passive"))
    )
    (net (code "39") (name "Net-(VTL1-COL)") (class "Default")
      (node (ref "DVT1") (pin "B") (pinfunction "B_B") (pintype "passive"))
      (node (ref "VTL1") (pin "4") (pinfunction "COL_4") (pintype "passive"))
    )
    (net (code "40") (name "Net-(VTL1-EMIT)") (class "Default")
      (node (ref "DVT1") (pin "C") (pinfunction "C_C") (pintype "passive"))
      (node (ref "R5") (pin "2") (pinfunction "2_2") (pintype "passive"))
      (node (ref "VTL1") (pin "3") (pinfunction "EMIT_3") (pintype "passive"))
    )
    (net (code "41") (name "PA14(TEST1)") (class "Default")
      (node (ref "SV4") (pin "5") (pinfunction "5_5") (pintype "passive"))
      (node (ref "X6") (pin "8") (pinfunction "8_8") (pintype "passive"))
    )
    (net (code "42") (name "PA16(COOL)") (class "Default")
      (node (ref "IC2") (pin "2") (pinfunction "IN_2") (pintype "input"))
      (node (ref "R22") (pin "1") (pinfunction "1_1") (pintype "passive"))
      (node (ref "SV4") (pin "6") (pinfunction "6_6") (pintype "passive"))
      (node (ref "X5") (pin "13") (pinfunction "13_13") (pintype "passive"))
    )
    (net (code "43") (name "PA17({slash}SW)") (class "Default")
      (node (ref "SV4") (pin "3") (pinfunction "3_3") (pintype "passive"))
      (node (ref "VTL1") (pin "2") (pinfunction "C_2") (pintype "passive"))
      (node (ref "X5") (pin "11") (pinfunction "11_11") (pintype "passive"))
    )
    (net (code "44") (name "PA18({slash}OUT)") (class "Default")
      (node (ref "IC1") (pin "2") (pinfunction "IN_2") (pintype "input"))
      (node (ref "OUT") (pin "1") (pinfunction "P_1") (pintype "passive"))
      (node (ref "SV4") (pin "8") (pinfunction "8_8") (pintype "passive"))
      (node (ref "X5") (pin "14") (pinfunction "14_14") (pintype "passive"))
    )
    (net (code "45") (name "PA19(TEST2)") (class "Default")
      (node (ref "SV4") (pin "7") (pinfunction "7_7") (pintype "passive"))
      (node (ref "X5") (pin "12") (pinfunction "12_12") (pintype "passive"))
    )
    (net (code "46") (name "PL") (class "Default")
      (node (ref "C12") (pin "+") (pinfunction "+_+") (pintype "passive"))
      (node (ref "C13") (pin "+") (pinfunction "+_+") (pintype "passive"))
      (node (ref "C14") (pin "+") (pinfunction "+_+") (pintype "passive"))
      (node (ref "C15") (pin "1") (pinfunction "1_1") (pintype "passive"))
      (node (ref "C16") (pin "1") (pinfunction "1_1") (pintype "passive"))
      (node (ref "C17") (pin "1") (pinfunction "1_1") (pintype "passive"))
      (node (ref "L1") (pin "1") (pinfunction "1_1") (pintype "passive"))
      (node (ref "L1") (pin "1@2") (pinfunction "1_1@2") (pintype "passive"))
      (node (ref "PL") (pin "1") (pinfunction "P_1") (pintype "passive"))
      (node (ref "PL2") (pin "1") (pinfunction "P_1") (pintype "passive"))
      (node (ref "VD10") (pin "C") (pinfunction "C_C") (pintype "passive"))
      (node (ref "VT2") (pin "2") (pinfunction "D_2") (pintype "passive"))
    )
    (net (code "47") (name "RX") (class "Default")
      (node (ref "SV4") (pin "1") (pinfunction "1_1") (pintype "passive"))
      (node (ref "UART") (pin "3") (pinfunction "3_3") (pintype "passive"))
      (node (ref "X6") (pin "12") (pinfunction "12_12") (pintype "passive"))
    )
    (net (code "48") (name "SH+") (class "Default")
      (node (ref "C34") (pin "1") (pinfunction "1_1") (pintype "passive"))
      (node (ref "R35") (pin "1") (pinfunction "1_1") (pintype "passive"))
      (node (ref "X6") (pin "4") (pinfunction "4_4") (pintype "passive"))
    )
    (net (code "49") (name "SH-") (class "Default")
      (node (ref "C34") (pin "2") (pinfunction "2_2") (pintype "passive"))
      (node (ref "R36") (pin "1") (pinfunction "1_1") (pintype "passive"))
      (node (ref "X6") (pin "3") (pinfunction "3_3") (pintype "passive"))
    )
    (net (code "50") (name "S_VT2") (class "Default")
      (node (ref "R10") (pin "2") (pinfunction "2_2") (pintype "passive"))
      (node (ref "R11") (pin "2") (pinfunction "2_2") (pintype "passive"))
      (node (ref "R12") (pin "2") (pinfunction "2_2") (pintype "passive"))
      (node (ref "R13") (pin "2") (pinfunction "2_2") (pintype "passive"))
      (node (ref "R14") (pin "1") (pinfunction "1_1") (pintype "passive"))
      (node (ref "VT2") (pin "3") (pinfunction "S_3") (pintype "passive"))
    )
    (net (code "51") (name "TX") (class "Default")
      (node (ref "SV4") (pin "2") (pinfunction "2_2") (pintype "passive"))
      (node (ref "UART") (pin "5") (pinfunction "5_5") (pintype "passive"))
      (node (ref "X6") (pin "11") (pinfunction "11_11") (pintype "passive"))
    )
    (net (code "52") (name "unconnected-(COOLER-Pad3)") (class "Default")
      (node (ref "COOLER") (pin "3") (pinfunction "3_3") (pintype "passive"))
    )
    (net (code "53") (name "unconnected-(SV4-Pad9)") (class "Default")
      (node (ref "SV4") (pin "9") (pinfunction "9_9") (pintype "passive"))
    )
    (net (code "54") (name "unconnected-(X5-Pad5)") (class "Default")
      (node (ref "X5") (pin "5") (pinfunction "5_5") (pintype "passive"))
    )
    (net (code "55") (name "unconnected-(X5-Pad8)") (class "Default")
      (node (ref "X5") (pin "8") (pinfunction "8_8") (pintype "passive"))
    )
    (net (code "56") (name "unconnected-(X5-Pad9)") (class "Default")
      (node (ref "X5") (pin "9") (pinfunction "9_9") (pintype "passive"))
    )
    (net (code "57") (name "unconnected-(X6-Pad1)") (class "Default")
      (node (ref "X6") (pin "1") (pinfunction "1_1") (pintype "passive"))
    )
    (net (code "58") (name "unconnected-(X6-Pad2)") (class "Default")
      (node (ref "X6") (pin "2") (pinfunction "2_2") (pintype "passive"))
    )
    (net (code "59") (name "unconnected-(X6-Pad5)") (class "Default")
      (node (ref "X6") (pin "5") (pinfunction "5_5") (pintype "passive"))
    )
    (net (code "60") (name "unconnected-(X6-Pad6)") (class "Default")
      (node (ref "X6") (pin "6") (pinfunction "6_6") (pintype "passive"))
    )
    (net (code "61") (name "unconnected-(X6-Pad7)") (class "Default")
      (node (ref "X6") (pin "7") (pinfunction "7_7") (pintype "passive"))
    )
    (net (code "62") (name "{slash}RESET") (class "Default")
      (node (ref "SV4") (pin "4") (pinfunction "4_4") (pintype "passive"))
      (node (ref "UART") (pin "7") (pinfunction "7_7") (pintype "passive"))
      (node (ref "X6") (pin "13") (pinfunction "13_13") (pintype "passive"))
    )
  )
)
